# AudioSubsystem.net
KiCad netlist of a schematic drawn in Altium Designer
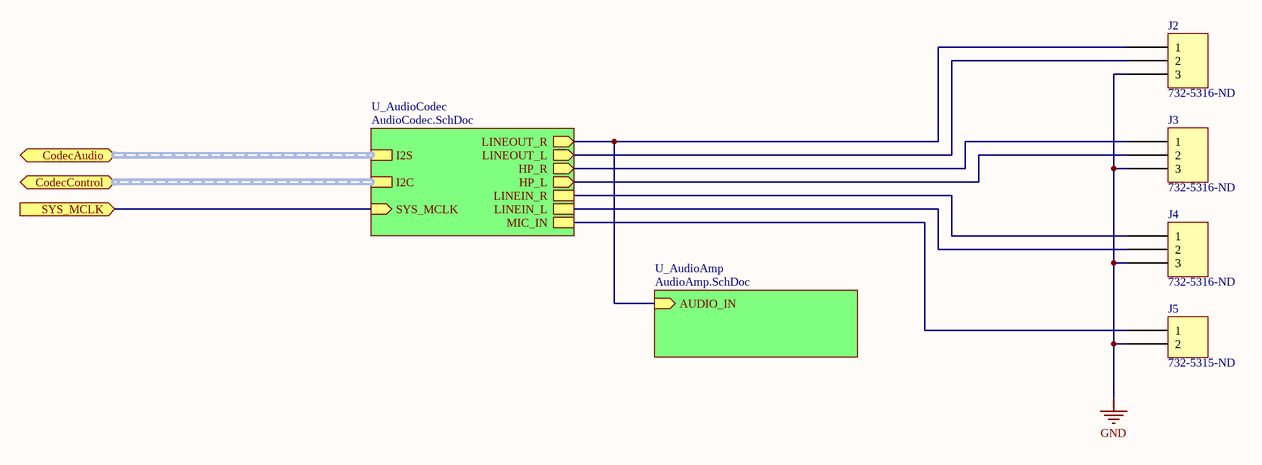
[diagram p0: AudioSubsystem.SchDoc]

(export (version "E")
  (design (tool "Eeschema 10.0.6"))
  (components
    (comp (ref "J2")
      (value "Header")
      (footprint "Pinhead_1x3")
      (fields (field (name "SUPPLIER PART NUMBER 1") "732-5316-ND"))
      (libsource (lib "Connectors") (part "3 Pin"))
    )
    (comp (ref "J3")
      (value "Header")
      (footprint "Pinhead_1x3")
      (fields (field (name "SUPPLIER PART NUMBER 1") "732-5316-ND"))
      (libsource (lib "Connectors") (part "3 Pin"))
    )
    (comp (ref "J4")
      (value "Header")
      (footprint "Pinhead_1x3")
      (fields (field (name "SUPPLIER PART NUMBER 1") "732-5316-ND"))
      (libsource (lib "Connectors") (part "3 Pin"))
    )
    (comp (ref "J5")
      (value "2 Pin")
      (footprint "Pinhead_1x2")
      (fields (field (name "SUPPLIER PART NUMBER 1") "732-5315-ND"))
      (libsource (lib "Connectors") (part "2 Pin"))
    )
  )
  (nets
    (net (code "5") (name "/HP_L") (class "Default")
      (node (ref "J3") (pin "2") (pinfunction "2_2") (pintype "passive"))
    )
    (net (code "6") (name "/HP_R") (class "Default")
      (node (ref "J3") (pin "1") (pinfunction "1_1") (pintype "passive"))
    )
    (net (code "7") (name "/LINEIN_L") (class "Default")
      (node (ref "J4") (pin "2") (pinfunction "2_2") (pintype "passive"))
    )
    (net (code "8") (name "/LINEIN_R") (class "Default")
      (node (ref "J4") (pin "1") (pinfunction "1_1") (pintype "passive"))
    )
    (net (code "9") (name "/LINEOUT_L") (class "Default")
      (node (ref "J2") (pin "2") (pinfunction "2_2") (pintype "passive"))
    )
    (net (code "10") (name "/LINEOUT_R") (class "Default")
      (node (ref "J2") (pin "1") (pinfunction "1_1") (pintype "passive"))
    )
    (net (code "11") (name "/MIC_IN") (class "Default")
      (node (ref "J5") (pin "1") (pinfunction "1_1") (pintype "passive"))
    )
    (net (code "13") (name "GND") (class "Default")
      (node (ref "J2") (pin "3") (pinfunction "3_3") (pintype "passive"))
      (node (ref "J3") (pin "3") (pinfunction "3_3") (pintype "passive"))
      (node (ref "J4") (pin "3") (pinfunction "3_3") (pintype "passive"))
      (node (ref "J5") (pin "2") (pinfunction "2_2") (pintype "passive"))
    )
  )
)
